# Miccrocontroller.net
KiCad netlist of a schematic drawn in Altium Designer
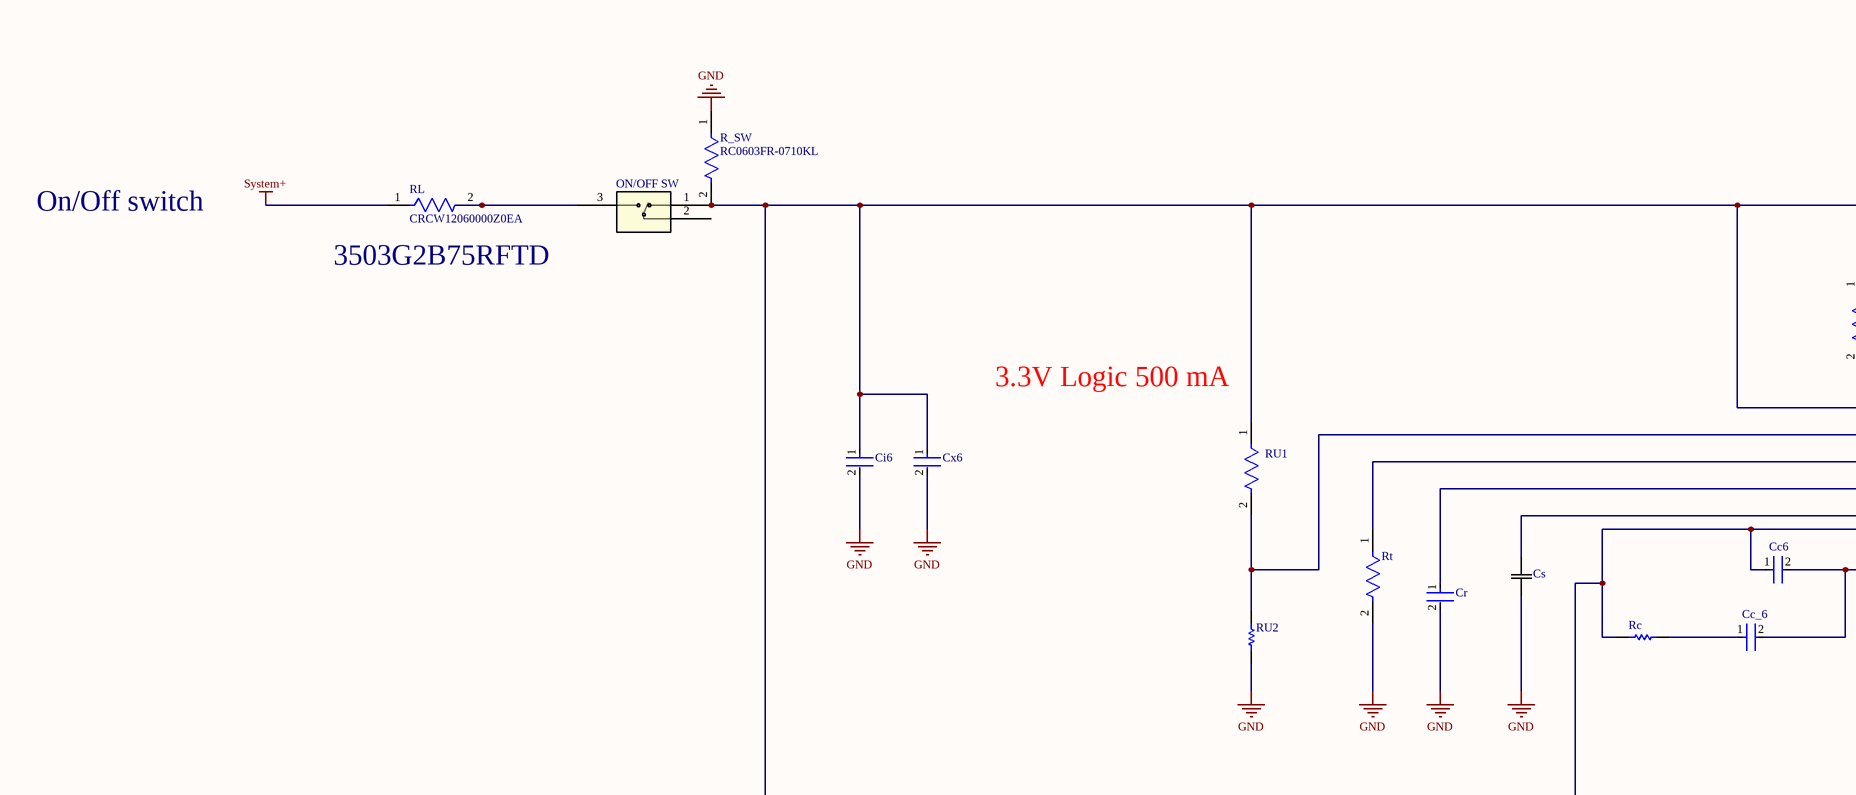
[diagram p0: Miccrocontroller.SchDoc, top left]
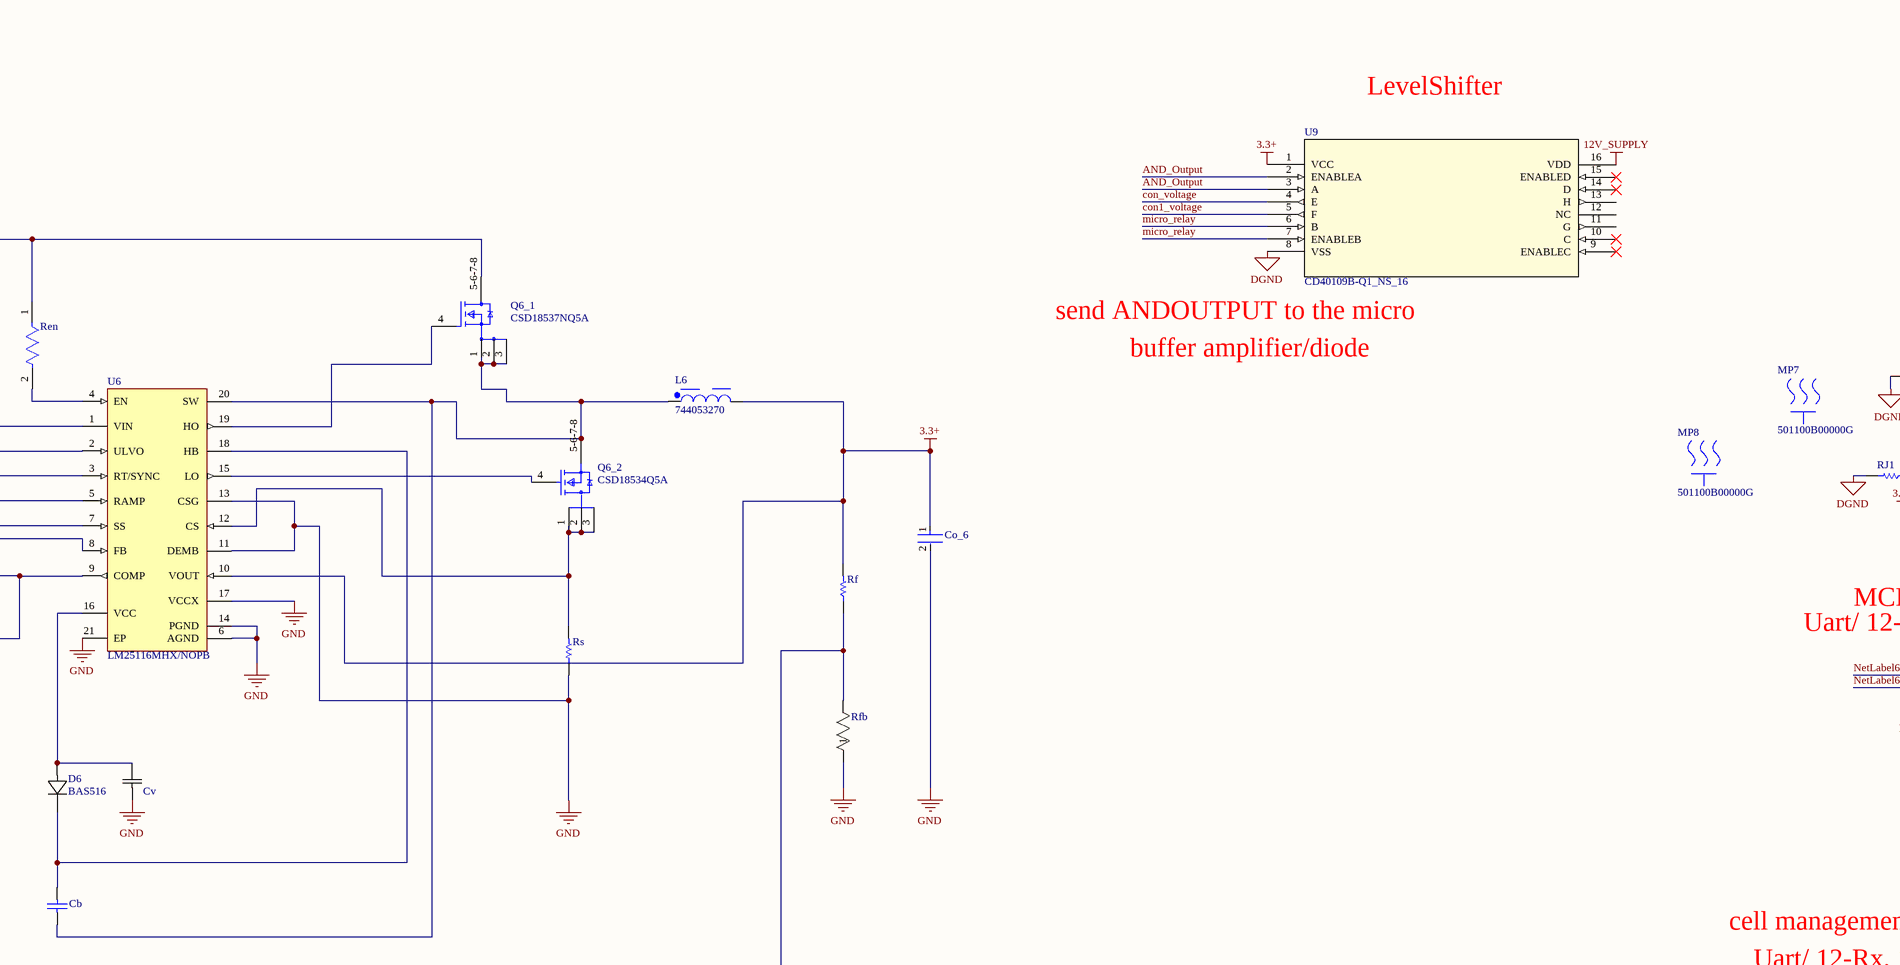
[diagram p1: Miccrocontroller.SchDoc, top middle]
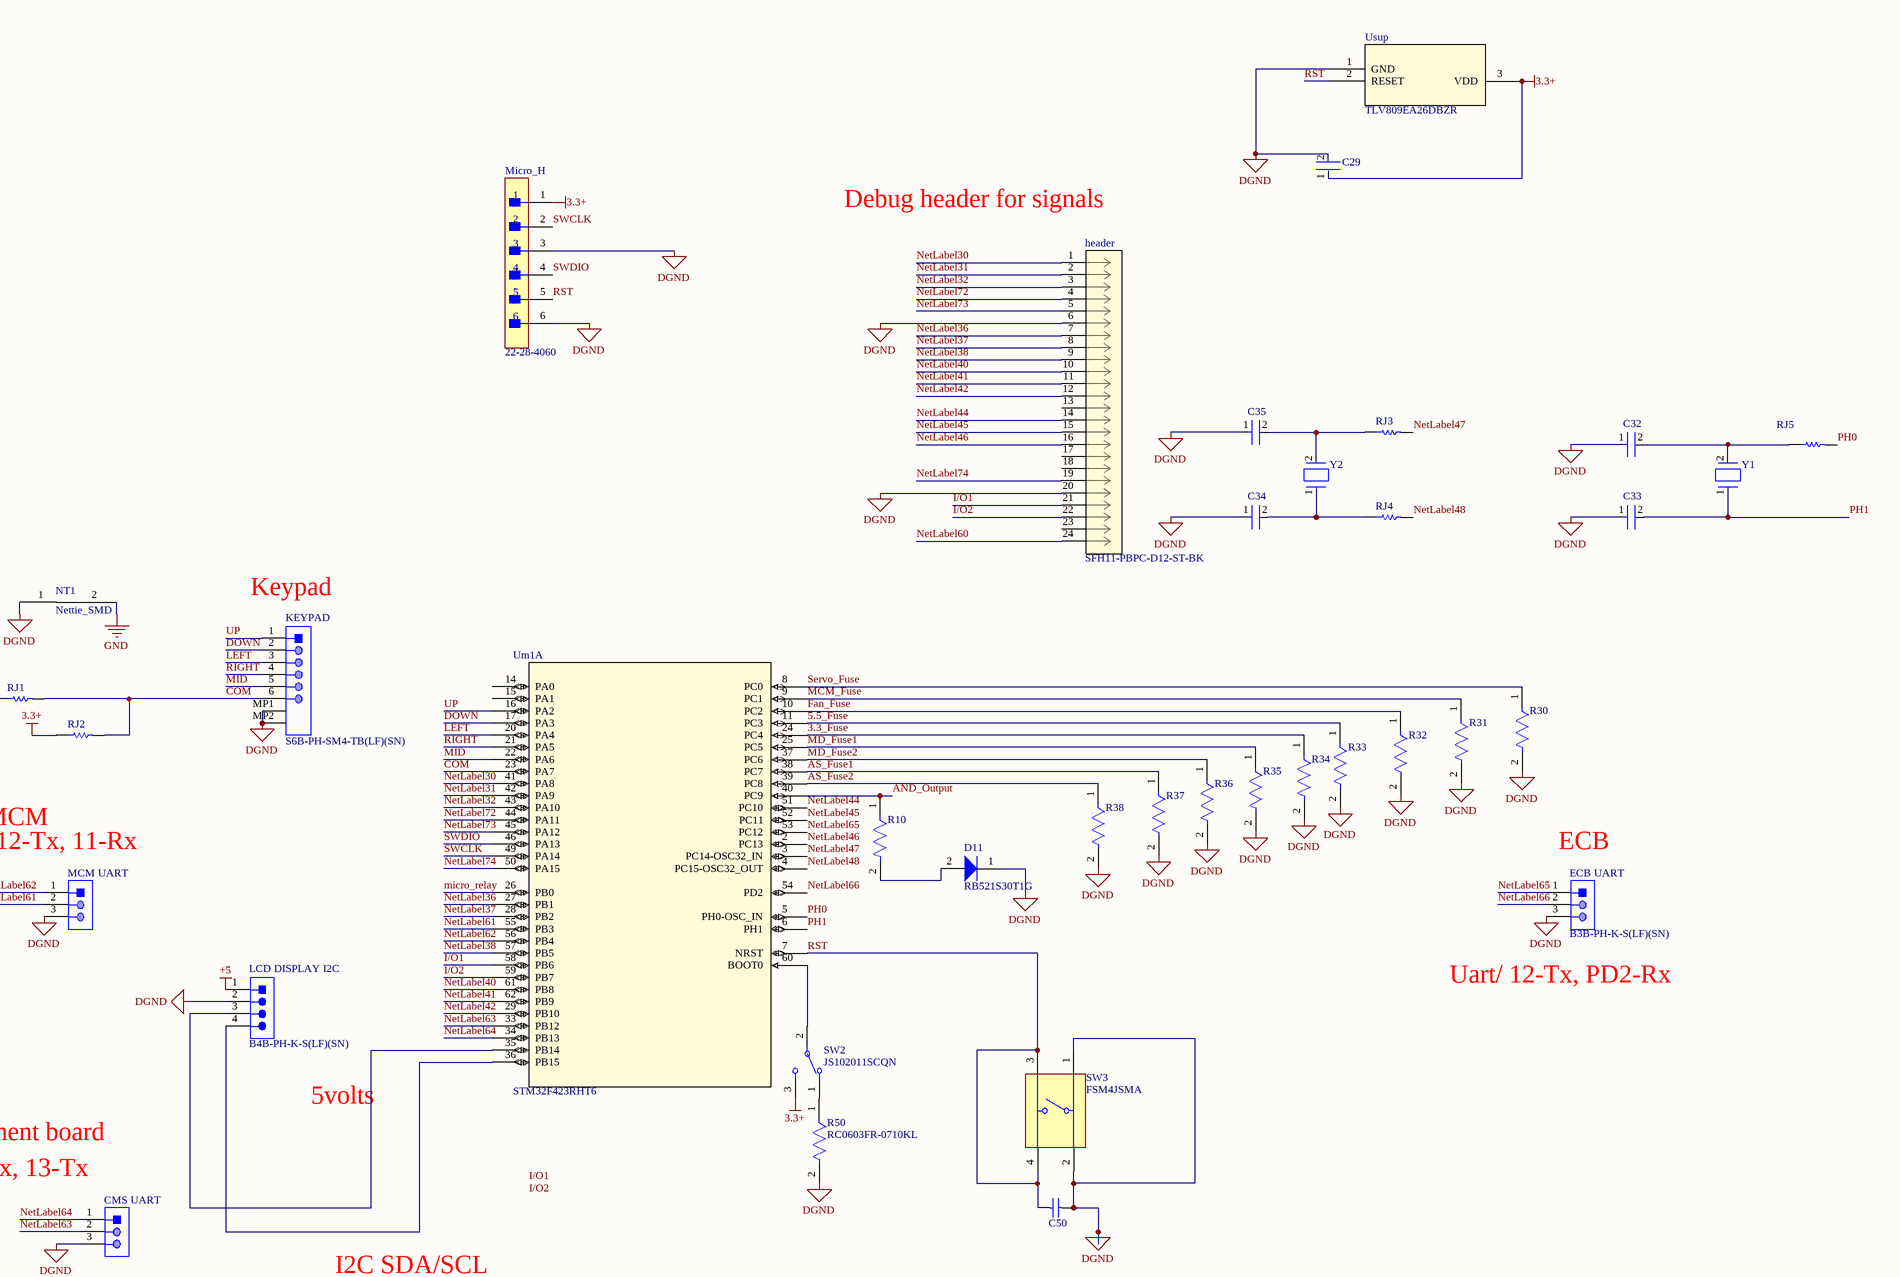
[diagram p2: Miccrocontroller.SchDoc, top right]
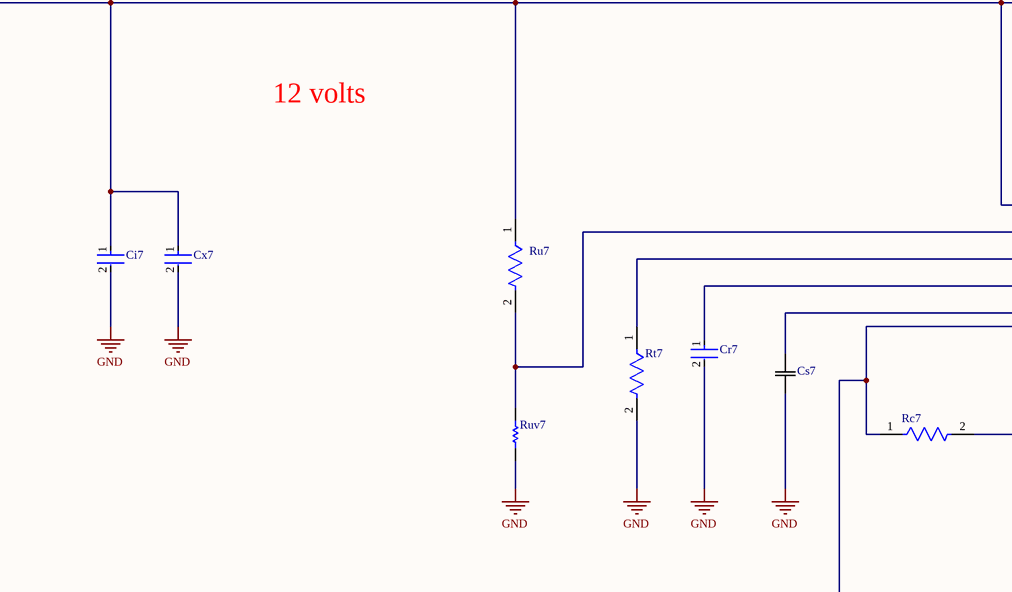
[diagram p3: Miccrocontroller.SchDoc, bottom left]
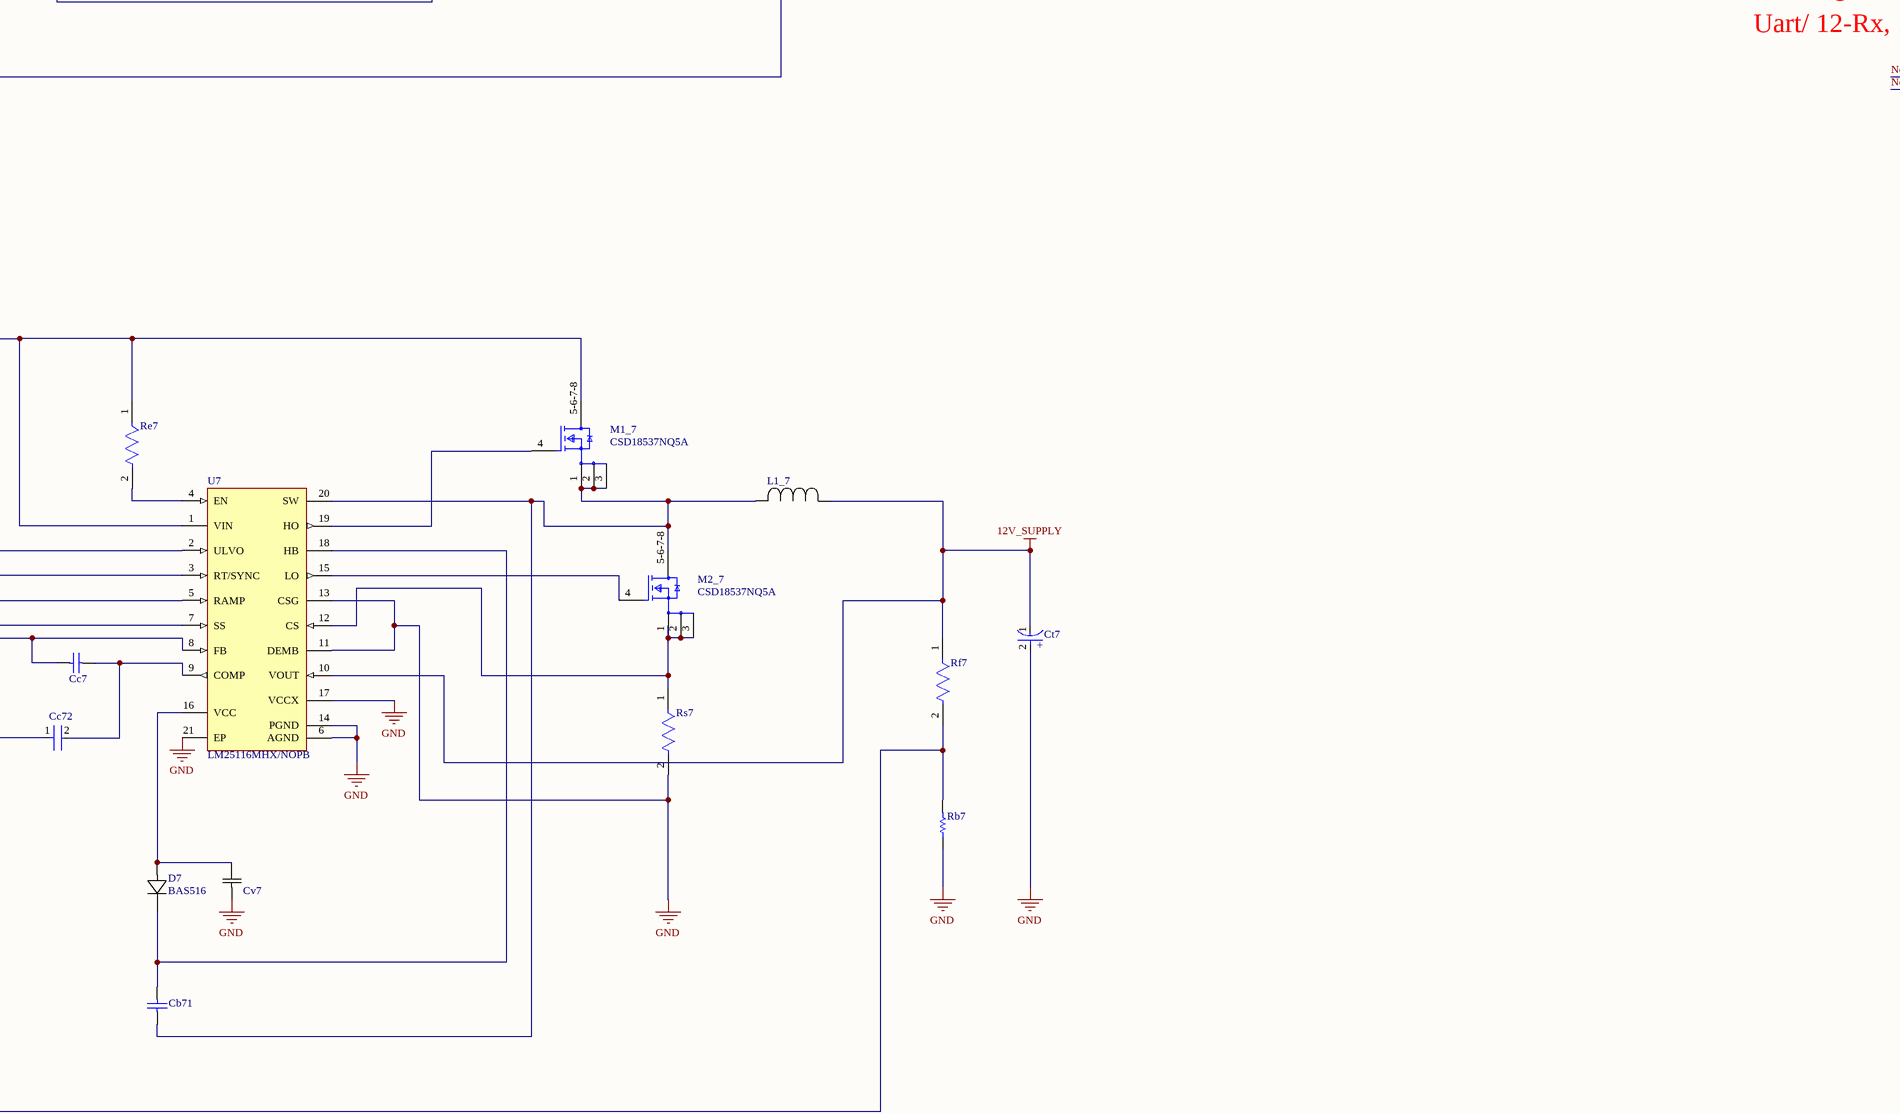
[diagram p4: Miccrocontroller.SchDoc, bottom middle]
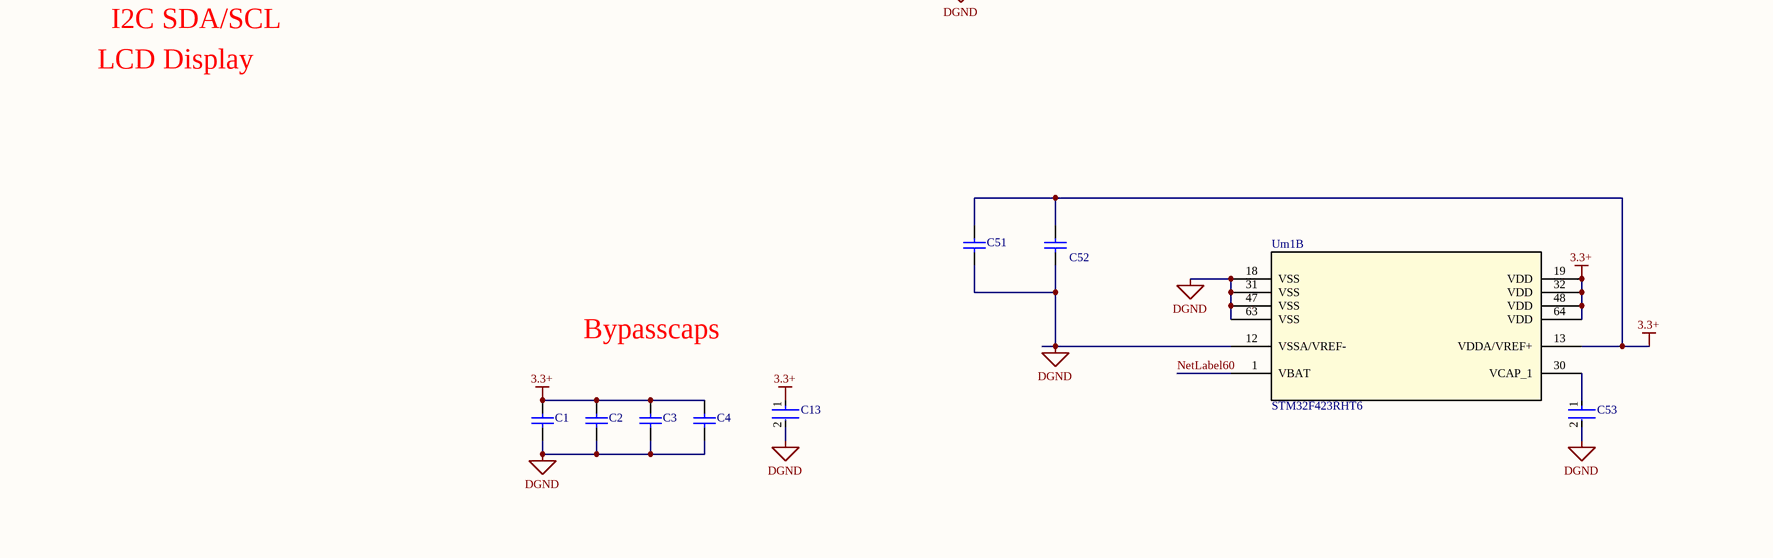
[diagram p5: Miccrocontroller.SchDoc, bottom right]

(export (version "E")
  (design (tool "Eeschema 10.0.6"))
  (components
    (comp (ref "C1")
      (value "06035C104KAT4A")
      (footprint "CAPC1608X90X35LL15T15")
      (fields (field (name "MANUFACTURER") "AVX Interconnect / Elco"))
      (libsource (lib "Altium Content Vault") (part "CAP"))
    )
    (comp (ref "C2")
      (value "06035C104KAT4A")
      (footprint "CAPC1608X90X35LL15T15")
      (fields (field (name "MANUFACTURER") "AVX Interconnect / Elco"))
      (libsource (lib "Altium Content Vault") (part "CAP"))
    )
    (comp (ref "C3")
      (value "06035C104KAT4A")
      (footprint "CAPC1608X90X35LL15T15")
      (fields (field (name "MANUFACTURER") "AVX Interconnect / Elco"))
      (libsource (lib "Altium Content Vault") (part "CAP"))
    )
    (comp (ref "C4")
      (value "06035C104KAT4A")
      (footprint "CAPC1608X90X35LL15T15")
      (fields (field (name "MANUFACTURER") "AVX Interconnect / Elco"))
      (libsource (lib "Altium Content Vault") (part "CAP"))
    )
    (comp (ref "C13")
      (value "GRM188R61E475KE11D")
      (footprint "FP-GRM188-0_15-IPC_C")
      (description "Chip Multilayer Ceramic Capacitors for General Purpose, 0603, 4.7uF, X5R, 15%, 10%, 25V")
      (fields (field (name "VOLTAGE") "25V") (field (name "TOLERANCE") "10%"))
      (libsource (lib "Altium Content Vault") (part "02cd4be3c70576c341d710602a673aa"))
    )
    (comp (ref "C29")
      (value "GRM155R71C104KA88D")
      (footprint "FP-GRM15-MFG")
      (description "CAP CER 0.1UF 16V X7R 0402")
      (fields
        (field (name "TOLERANCE") "10%")
        (field (name "OCTOPART") "https://octopart.com/grm155r71c104ka88d-murata-196880")
      )
      (libsource (lib "Altium Content Vault") (part "236180d848d6139a670b325ea6854c9"))
    )
    (comp (ref "C32")
      (value "C0805C180J5GACTU")
      (footprint "FP-C0805C-DN-MFG")
      (description "CAP CER 18PF 50V C0G/NP0 0805")
      (fields
        (field (name "OCTOPART") "https://octopart.com/c0805c180j5gactu-kemet-144810")
        (field (name "TOLERANCE") "0.05")
      )
      (libsource (lib "Altium Content Vault") (part "b4654b650e69147ec39a6b967a45e02"))
    )
    (comp (ref "C33")
      (value "C0805C180J5GACTU")
      (footprint "FP-C0805C-DN-MFG")
      (description "CAP CER 18PF 50V C0G/NP0 0805")
      (fields
        (field (name "OCTOPART") "https://octopart.com/c0805c180j5gactu-kemet-144810")
        (field (name "TOLERANCE") "0.05")
      )
      (libsource (lib "Altium Content Vault") (part "b4654b650e69147ec39a6b967a45e02"))
    )
    (comp (ref "C34")
      (value "GJM1555C1H1R5BB01D")
      (footprint "FP-GJM155-0_05-IPC_C")
      (description "Multi-Layer Ceramic Capacitor 1.5pF C0G  ±0.1pF 0402 Paper T/R")
      (fields (field (name "VOLTAGE") "50V"))
      (libsource (lib "Altium Content Vault") (part "02cd4be3c70576c341d710602a673aa"))
    )
    (comp (ref "C35")
      (value "GJM1555C1H1R5BB01D")
      (footprint "FP-GJM155-0_05-IPC_C")
      (description "Multi-Layer Ceramic Capacitor 1.5pF C0G  ±0.1pF 0402 Paper T/R")
      (fields (field (name "VOLTAGE") "50V"))
      (libsource (lib "Altium Content Vault") (part "02cd4be3c70576c341d710602a673aa"))
    )
    (comp (ref "C50")
      (value "06035C104KAT4A")
      (footprint "CAPC1608X90X35LL15T15")
      (fields (field (name "MANUFACTURER") "AVX Interconnect / Elco"))
      (libsource (lib "Altium Content Vault") (part "CAP"))
    )
    (comp (ref "C51")
      (value "C0603C105K3RACTU")
      (footprint "CAPC1608X87X35LL15T15")
      (fields (field (name "MANUFACTURER") "Kemet"))
      (libsource (lib "Altium Content Vault") (part "CAP"))
    )
    (comp (ref "C52")
      (value "06035C104KAT4A")
      (footprint "CAPC1608X90X35LL15T15")
      (fields (field (name "MANUFACTURER") "AVX Interconnect / Elco"))
      (libsource (lib "Altium Content Vault") (part "CAP"))
    )
    (comp (ref "C53")
      (value "GRM188R71A225KE15D")
      (footprint "FP-GRM188-0_1-e0_2_0_5-MFG")
      (description "Chip Multilayer Ceramic Capacitors for General Purpose, 0603, 2.2uF, X7R, 15%, 10%, 10V")
      (fields (field (name "VOLTAGE") "10V") (field (name "TOLERANCE") "10%"))
      (libsource (lib "Altium Content Vault") (part "11868f565c42a9108669ba33697ecf6"))
    )
    (comp (ref "Cb")
      (value "08053C104K4T2A")
      (footprint "CAPC2013X140X50LL20T25")
      (fields (field (name "MANUFACTURER") "AVX Interconnect / Elco"))
      (libsource (lib "Altium Content Vault") (part "CAP"))
    )
    (comp (ref "Cb71")
      (value "08053C104K4T2A")
      (footprint "CAPC2013X140X50LL20T25")
      (fields (field (name "MANUFACTURER") "AVX Interconnect / Elco"))
      (libsource (lib "Altium Content Vault") (part "CAP"))
    )
    (comp (ref "Cc6")
      (value "C0805C100M4GACTU")
      (footprint "FP-C0805C-DN-MFG")
      (description "CAP CER 10PF 16V 20% NP0 0805")
      (fields
        (field (name "OCTOPART") "https://octopart.com/c0805c100m4gactu-kemet-16430157")
        (field (name "TOLERANCE") "0.2")
      )
      (libsource (lib "Altium Content Vault") (part "b4654b650e69147ec39a6b967a45e02"))
    )
    (comp (ref "Cc7")
      (value "GRM1555C1E5R1CA01D")
      (footprint "CAPC1005X55X25LL05T10")
      (fields (field (name "MANUFACTURER") "Murata"))
      (libsource (lib "Altium Content Vault") (part "CAP"))
    )
    (comp (ref "Cc72")
      (value "GRM1555C1H101FA01D")
      (footprint "FP-GRM155-0_05-IPC_C")
      (description "CAP CER 100PF 50V C0G/NP0 0402")
      (fields (field (name "VOLTAGE") "50V") (field (name "TOLERANCE") "1%"))
      (libsource (lib "Altium Content Vault") (part "b4654b650e69147ec39a6b967a45e02"))
    )
    (comp (ref "Cc_6")
      (value "UMK105CG271JV-F")
      (footprint "FP-0402-L_1_0_0_05-W_0_5-IPC_B")
      (description "None")
      (fields (field (name "TOLERANCE") "5%"))
      (libsource (lib "Altium Content Vault") (part "b4654b650e69147ec39a6b967a45e02"))
    )
    (comp (ref "Ci6")
      (value "GRM31CR71H475KA12L")
      (footprint "FP-GRM31C-0_2-e0_3_0_8-IPC_C")
      (description "Chip Multilayer Ceramic Capacitors for General Purpose, 1206, 4.7uF, X7R, 15%, 10%, 50V")
      (fields (field (name "VOLTAGE") "50V") (field (name "TOLERANCE") "10%"))
      (libsource (lib "Altium Content Vault") (part "02cd4be3c70576c341d710602a673aa"))
    )
    (comp (ref "Ci7")
      (value "GRM31CR71H475KA12L")
      (footprint "FP-GRM31C-0_2-e0_3_0_8-IPC_C")
      (description "Chip Multilayer Ceramic Capacitors for General Purpose, 1206, 4.7uF, X7R, 15%, 10%, 50V")
      (fields (field (name "VOLTAGE") "50V") (field (name "TOLERANCE") "10%"))
      (libsource (lib "Altium Content Vault") (part "02cd4be3c70576c341d710602a673aa"))
    )
    (comp (ref "CMS UART")
      (value "B3B-PH-K-S(LF)(SN)")
      (footprint "JST-B3B-PH-K-S-3_V")
      (fields (field (name "MANUFACTURER") "JST"))
      (libsource (lib "Altium Content Vault") (part "CN-1P-M-R3"))
    )
    (comp (ref "Co_6")
      (value "C0805C475K8PACTU")
      (footprint "FP-C0805C475K8PACTU-MFG")
      (description "CAP CER 4.7UF 10V X5R 0805")
      (fields (field (name "TOLERANCE") "10%") (field (name "VOLTAGE") "10V"))
      (libsource (lib "Altium Content Vault") (part "e9c51b7dd13d4faca003ae77663ab08"))
    )
    (comp (ref "Cr")
      (value "GRM1555C1H101FA01D")
      (footprint "FP-GRM155-0_05-IPC_C")
      (description "CAP CER 100PF 50V C0G/NP0 0402")
      (fields (field (name "VOLTAGE") "50V") (field (name "TOLERANCE") "1%"))
      (libsource (lib "Altium Content Vault") (part "b4654b650e69147ec39a6b967a45e02"))
    )
    (comp (ref "Cr7")
      (value "UMK105CG271JV-F")
      (footprint "FP-0402-L_1_0_0_05-W_0_5-IPC_B")
      (description "None")
      (fields (field (name "TOLERANCE") "5%"))
      (libsource (lib "Altium Content Vault") (part "b4654b650e69147ec39a6b967a45e02"))
    )
    (comp (ref "Cs")
      (value "CGA4J2C0G1H333J125AA")
      (footprint "CAP_2012_TDK-M")
      (description "No Description Available")
      (libsource (lib "CGA4J2C0G1H333J125AA") (part "CGA4J2C0G1H333J125AA"))
    )
    (comp (ref "Cs7")
      (value "CGA4J2C0G1H333J125AA")
      (footprint "CAP_2012_TDK-M")
      (description "No Description Available")
      (libsource (lib "CGA4J2C0G1H333J125AA") (part "CGA4J2C0G1H333J125AA"))
    )
    (comp (ref "Ct7")
      (value "25SVPF27MX")
      (footprint "FP-OS-CON-SMT-B6-MFG")
      (description "Conductive Polymer Aluminum Solid Capacitors (OS-CON) 27uF ±20% 25V")
      (fields (field (name "VOLTAGE") "25V") (field (name "TOLERANCE") "20%"))
      (libsource (lib "Altium Content Vault") (part "a00bbbee19879c290e62620ae7e47b1"))
    )
    (comp (ref "Cv")
      (value "TMK212BJ105KG-T")
      (footprint "CAP_TMK212BJ105KG-T_TAY")
      (description "No Description Available")
      (libsource (lib "TMK212BJ105KG-T") (part "TMK212BJ105KG-T"))
    )
    (comp (ref "Cv7")
      (value "TMK212BJ105KG-T")
      (footprint "CAP_TMK212BJ105KG-T_TAY")
      (description "No Description Available")
      (libsource (lib "TMK212BJ105KG-T") (part "TMK212BJ105KG-T"))
    )
    (comp (ref "Cx6")
      (value "C0805C104M5RACTU")
      (footprint "FP-C0805C-DN-MFG")
      (description "CAP CER 0.1UF 50V X7R 0805")
      (fields
        (field (name "TOLERANCE") "0.2")
        (field (name "OCTOPART") "https://octopart.com/c0805c104m5ractu-kemet-129379")
      )
      (libsource (lib "Altium Content Vault") (part "b4654b650e69147ec39a6b967a45e02"))
    )
    (comp (ref "Cx7")
      (value "C0805C104M5RACTU")
      (footprint "FP-C0805C-DN-MFG")
      (description "CAP CER 0.1UF 50V X7R 0805")
      (fields
        (field (name "TOLERANCE") "0.2")
        (field (name "OCTOPART") "https://octopart.com/c0805c104m5ractu-kemet-129379")
      )
      (libsource (lib "Altium Content Vault") (part "b4654b650e69147ec39a6b967a45e02"))
    )
    (comp (ref "D6")
      (value "BAS516")
      (footprint "SOD523_NEX")
      (description "No Description Available")
      (libsource (lib "BAS516") (part "BAS516"))
    )
    (comp (ref "D7")
      (value "BAS516")
      (footprint "SOD523_NEX")
      (description "No Description Available")
      (libsource (lib "BAS516") (part "BAS516"))
    )
    (comp (ref "D11")
      (value "RB521S30T1G")
      (footprint "ONSC-SOD-523-2-502-01_V")
      (description "Schottky Barrier Diode, 2-Pin SOD-523, Pb-Free, Tape and Reel")
      (fields (field (name "MANUFACTURER") "On Semiconductor"))
      (libsource (lib "Altium Content Vault") (part "ONSC-D-K1A2-2"))
    )
    (comp (ref "ECB UART")
      (value "B3B-PH-K-S(LF)(SN)")
      (footprint "JST-B3B-PH-K-S-3_V")
      (fields (field (name "MANUFACTURER") "JST"))
      (libsource (lib "Altium Content Vault") (part "CN-1P-M-R3"))
    )
    (comp (ref "header")
      (value "SFH11-PBPC-D12-ST-BK")
      (footprint "CONN_SFH11-PBPC-D12-ST-BK")
      (description "No Description Available")
      (libsource (lib "SFH11-PBPC-D12-ST-BK") (part "SFH11-PBPC-D12-ST-BK"))
    )
    (comp (ref "KEYPAD")
      (value "S6B-PH-SM4-TB(LF)(SN)")
      (footprint "JST-S6B-PH-SM4-TB(LF)(SN)_V")
      (description "Male Header, Pitch 2 mm, 1 x 6 Position, Height 5.5 mm, -25 to 85 degC")
      (fields (field (name "MANUFACTURER") "JST"))
      (libsource (lib "Altium Content Vault") (part "CN-1P-2M-R6"))
    )
    (comp (ref "L1_7")
      (value "MSS1038-123MLB")
      (footprint "IND_MSS1038_COC")
      (description "No Description Available")
      (libsource (lib "MSS1038-123MLB") (part "MSS1038-123MLB"))
    )
    (comp (ref "L6")
      (value "744053270")
      (footprint "WE-TPC_5828")
      (libsource (lib "Altium Content Vault") (part "Inductor - 2"))
    )
    (comp (ref "LCD DISPLAY I2C")
      (value "B4B-PH-K-S(LF)(SN)")
      (footprint "JST-B4B-PH-K-S_V")
      (fields (field (name "MANUFACTURER") "JST"))
      (libsource (lib "Altium Content Vault") (part "CN-1P-M-R4"))
    )
    (comp (ref "M1_7")
      (value "CSD18537NQ5A")
      (footprint "FP-DQJ0008A-MFG")
      (description "MOSFET N-CH 60V 50A 8SON")
      (libsource (lib "Altium Content Vault") (part "7382af88e928fdc71488234cfaaf11c"))
    )
    (comp (ref "M2_7")
      (value "CSD18537NQ5A")
      (footprint "FP-DQJ0008A-MFG")
      (description "MOSFET N-CH 60V 50A 8SON")
      (libsource (lib "Altium Content Vault") (part "7382af88e928fdc71488234cfaaf11c"))
    )
    (comp (ref "MCM UART")
      (value "B3B-PH-K-S(LF)(SN)")
      (footprint "JST-B3B-PH-K-S-3_V")
      (fields (field (name "MANUFACTURER") "JST"))
      (libsource (lib "Altium Content Vault") (part "CN-1P-M-R3"))
    )
    (comp (ref "Micro_H")
      (value "22-28-4060")
      (footprint "FP-22-28-4060-MFG")
      (description "CONN HEADER VERT 6POS 2.54MM")
      (libsource (lib "Altium Content Vault") (part "f2cb566baf1c37ab5a3b8e90bbeafd6"))
    )
    (comp (ref "MP7")
      (value "501100B00000G")
      (footprint "FP-501100B00000G-MFG")
      (description "HEATSINK 14-DIP/16-DIP")
      (libsource (lib "Altium Content Vault") (part "fbfed2df5ada343d60df597a9663bc7"))
    )
    (comp (ref "MP8")
      (value "501100B00000G")
      (footprint "FP-501100B00000G-MFG")
      (description "HEATSINK 14-DIP/16-DIP")
      (libsource (lib "Altium Content Vault") (part "fbfed2df5ada343d60df597a9663bc7"))
    )
    (comp (ref "NT1")
      (value "Nettie_SMD")
      (footprint "Nettie_SMD")
      (libsource (lib "Schlib1") (part "Nettie_SMD"))
    )
    (comp (ref "ON/OFF SW")
      (value "100SP1T1B4M2QE")
      (footprint "100SP1T1_EWI")
      (description "No Description Available")
      (libsource (lib "100SP1T1B4M2QE") (part "100SP1T1B4M2QE"))
    )
    (comp (ref "Q6_1")
      (value "CSD18537NQ5A")
      (footprint "FP-DQJ0008A-MFG")
      (description "MOSFET N-CH 60V 50A 8SON")
      (libsource (lib "Altium Content Vault") (part "7382af88e928fdc71488234cfaaf11c"))
    )
    (comp (ref "Q6_2")
      (value "CSD18534Q5A")
      (footprint "FP-DQJ0008A-MFG")
      (description "MOSFET N-CH 60V 8SON")
      (fields
        (field (name "OCTOPART") "https://octopart.com/csd18534q5a-texas+instruments-22791040")
        (field (name "MANUFACTURER") "Texas Instruments")
      )
      (libsource (lib "Altium Content Vault") (part "2b493a92fcdc54dddf28a3aa2503ef1"))
    )
    (comp (ref "R10")
      (value "RC0603FR-0710KL")
      (footprint "FP-RC0603-0_55-IPC_C")
      (description "RES 10K OHM 1% 1/10W 0603")
      (fields (field (name "TOLERANCE") "1%"))
      (libsource (lib "Altium Content Vault") (part "1029c3af85768c4190bb7ad29bc67b5"))
    )
    (comp (ref "R30")
      (value "RC0603FR-0710KL")
      (footprint "FP-RC0603-0_55-IPC_C")
      (description "RES 10K OHM 1% 1/10W 0603")
      (fields (field (name "TOLERANCE") "1%"))
      (libsource (lib "Altium Content Vault") (part "1029c3af85768c4190bb7ad29bc67b5"))
    )
    (comp (ref "R31")
      (value "RC0603FR-0710KL")
      (footprint "FP-RC0603-0_55-IPC_C")
      (description "RES 10K OHM 1% 1/10W 0603")
      (fields (field (name "TOLERANCE") "1%"))
      (libsource (lib "Altium Content Vault") (part "1029c3af85768c4190bb7ad29bc67b5"))
    )
    (comp (ref "R32")
      (value "RC0603FR-0710KL")
      (footprint "FP-RC0603-0_55-IPC_C")
      (description "RES 10K OHM 1% 1/10W 0603")
      (fields (field (name "TOLERANCE") "1%"))
      (libsource (lib "Altium Content Vault") (part "1029c3af85768c4190bb7ad29bc67b5"))
    )
    (comp (ref "R33")
      (value "RC0603FR-0710KL")
      (footprint "FP-RC0603-0_55-IPC_C")
      (description "RES 10K OHM 1% 1/10W 0603")
      (fields (field (name "TOLERANCE") "1%"))
      (libsource (lib "Altium Content Vault") (part "1029c3af85768c4190bb7ad29bc67b5"))
    )
    (comp (ref "R34")
      (value "RC0603FR-0710KL")
      (footprint "FP-RC0603-0_55-IPC_C")
      (description "RES 10K OHM 1% 1/10W 0603")
      (fields (field (name "TOLERANCE") "1%"))
      (libsource (lib "Altium Content Vault") (part "1029c3af85768c4190bb7ad29bc67b5"))
    )
    (comp (ref "R35")
      (value "RC0603FR-0710KL")
      (footprint "FP-RC0603-0_55-IPC_C")
      (description "RES 10K OHM 1% 1/10W 0603")
      (fields (field (name "TOLERANCE") "1%"))
      (libsource (lib "Altium Content Vault") (part "1029c3af85768c4190bb7ad29bc67b5"))
    )
    (comp (ref "R36")
      (value "RC0603FR-0710KL")
      (footprint "FP-RC0603-0_55-IPC_C")
      (description "RES 10K OHM 1% 1/10W 0603")
      (fields (field (name "TOLERANCE") "1%"))
      (libsource (lib "Altium Content Vault") (part "1029c3af85768c4190bb7ad29bc67b5"))
    )
    (comp (ref "R37")
      (value "RC0603FR-0710KL")
      (footprint "FP-RC0603-0_55-IPC_C")
      (description "RES 10K OHM 1% 1/10W 0603")
      (fields (field (name "TOLERANCE") "1%"))
      (libsource (lib "Altium Content Vault") (part "1029c3af85768c4190bb7ad29bc67b5"))
    )
    (comp (ref "R38")
      (value "RC0603FR-0710KL")
      (footprint "FP-RC0603-0_55-IPC_C")
      (description "RES 10K OHM 1% 1/10W 0603")
      (fields (field (name "TOLERANCE") "1%"))
      (libsource (lib "Altium Content Vault") (part "1029c3af85768c4190bb7ad29bc67b5"))
    )
    (comp (ref "R50")
      (value "RC0603FR-0710KL")
      (footprint "FP-RC0603-0_55-IPC_C")
      (description "RES 10K OHM 1% 1/10W 0603")
      (fields (field (name "TOLERANCE") "1%"))
      (libsource (lib "Altium Content Vault") (part "1029c3af85768c4190bb7ad29bc67b5"))
    )
    (comp (ref "Rb7")
      (value "ERJ-6ENF9761V")
      (footprint "RESC2013X70X40ML20T20")
      (fields (field (name "MANUFACTURER") "Panasonic"))
      (libsource (lib "Altium Content Vault") (part "RES"))
    )
    (comp (ref "Rc")
      (value "RC0402FR-0768K1L")
      (footprint "RESC1005X40X25NL05T10")
      (fields (field (name "MANUFACTURER") "Yageo / Phycomp"))
      (libsource (lib "Altium Content Vault") (part "RES"))
    )
    (comp (ref "Rc7")
      (value "CRCW0402191KFKED")
      (footprint "FP-CRCW0402-e3-IPC_C")
      (description "RES Thick Film, 191kΩ, 1%, 0.063W, 100ppm/°C, 0402")
      (fields (field (name "TOLERANCE") "1%"))
      (libsource (lib "Altium Content Vault") (part "1029c3af85768c4190bb7ad29bc67b5"))
    )
    (comp (ref "Re7")
      (value "CRCW04021M00FKED")
      (footprint "FP-CRCW0402-e3-MFG")
      (description "RES Thick Film, 1MΩ, 1%, 0.063W, 100ppm/°C, 0402")
      (fields (field (name "TOLERANCE") "1%"))
      (libsource (lib "Altium Content Vault") (part "1029c3af85768c4190bb7ad29bc67b5"))
    )
    (comp (ref "Ren")
      (value "CRCW04021M00FKED")
      (footprint "FP-CRCW0402-e3-MFG")
      (description "RES Thick Film, 1MΩ, 1%, 0.063W, 100ppm/°C, 0402")
      (fields (field (name "TOLERANCE") "1%"))
      (libsource (lib "Altium Content Vault") (part "1029c3af85768c4190bb7ad29bc67b5"))
    )
    (comp (ref "Rf")
      (value "ERJ-6ENF1872V")
      (footprint "RESC2013X70X40LL20T20")
      (fields (field (name "MANUFACTURER") "Panasonic"))
      (libsource (lib "Altium Content Vault") (part "RES"))
    )
    (comp (ref "Rf7")
      (value "AC0402FR-0786K6L")
      (footprint "FP-AC0402-IPC_B")
      (description "RES 86.6kΩ ±1% 0.063W 0402")
      (fields (field (name "TOLERANCE") "1%"))
      (libsource (lib "Altium Content Vault") (part "1029c3af85768c4190bb7ad29bc67b5"))
    )
    (comp (ref "Rfb")
      (value "RNCF0805BTE10K4")
      (footprint "RES_RNCF0805_STP")
      (description "No Description Available")
      (libsource (lib "RNCF0805BTE10K4") (part "RNCF0805BTE10K4"))
    )
    (comp (ref "RJ1")
      (value "CRCW08050000Z0EA")
      (footprint "RESC2013X50X30LL20T20")
      (fields (field (name "MANUFACTURER") "Vishay Dale"))
      (libsource (lib "Altium Content Vault") (part "RES"))
    )
    (comp (ref "RJ2")
      (value "CRCW08050000Z0EA")
      (footprint "RESC2013X50X30LL20T20")
      (fields (field (name "MANUFACTURER") "Vishay Dale"))
      (libsource (lib "Altium Content Vault") (part "RES"))
    )
    (comp (ref "RJ3")
      (value "CRCW08050000Z0EA")
      (footprint "RESC2013X50X30LL20T20")
      (fields (field (name "MANUFACTURER") "Vishay Dale"))
      (libsource (lib "Altium Content Vault") (part "RES"))
    )
    (comp (ref "RJ4")
      (value "CRCW08050000Z0EA")
      (footprint "RESC2013X50X30LL20T20")
      (fields (field (name "MANUFACTURER") "Vishay Dale"))
      (libsource (lib "Altium Content Vault") (part "RES"))
    )
    (comp (ref "RJ5")
      (value "CRCW08050000Z0EA")
      (footprint "RESC2013X50X30LL20T20")
      (fields (field (name "MANUFACTURER") "Vishay Dale"))
      (libsource (lib "Altium Content Vault") (part "RES"))
    )
    (comp (ref "RL")
      (value "CRCW12060000Z0EA")
      (footprint "FP-CRCW1206-e3-IPC_C")
      (description "RES Thick Film, 0Ω, 0.25W, 1206")
      (fields (field (name "TOLERANCE") "1%"))
      (libsource (lib "Altium Content Vault") (part "1029c3af85768c4190bb7ad29bc67b5"))
    )
    (comp (ref "Rs")
      (value "ERJ-3RSFR15V")
      (footprint "RESC1608X55X30ML15T15")
      (fields (field (name "MANUFACTURER") "Panasonic"))
      (libsource (lib "Altium Content Vault") (part "RES"))
    )
    (comp (ref "Rs7")
      (value "CSR1206FK15L0")
      (footprint "FP-CSR1206-IPC_B")
      (description "General Purpose Thick Film Chip Resistor, 1206, 15mΩ, 1%, 0.5W")
      (fields (field (name "TOLERANCE") "1%"))
      (libsource (lib "Altium Content Vault") (part "1029c3af85768c4190bb7ad29bc67b5"))
    )
    (comp (ref "Rt")
      (value "CRCW04025K23FKED")
      (footprint "FP-CRCW0402-e3-IPC_C")
      (description "RES Thick Film, 5.23kΩ, 1%, 0.063W, 100ppm/°C, 0402")
      (fields (field (name "TOLERANCE") "1%"))
      (libsource (lib "Altium Content Vault") (part "1029c3af85768c4190bb7ad29bc67b5"))
    )
    (comp (ref "Rt7")
      (value "CRCW04025K23FKED")
      (footprint "FP-CRCW0402-e3-IPC_C")
      (description "RES Thick Film, 5.23kΩ, 1%, 0.063W, 100ppm/°C, 0402")
      (fields (field (name "TOLERANCE") "1%"))
      (libsource (lib "Altium Content Vault") (part "1029c3af85768c4190bb7ad29bc67b5"))
    )
    (comp (ref "RU1")
      (value "CRCW080541K2FKEA")
      (footprint "Vishay_CRCW0805-e3_MFG")
      (fields (field (name "TOLERANCE") "1%"))
      (libsource (lib "Altium Content Vault") (part "CRCW080541K2FKEA"))
    )
    (comp (ref "RU2")
      (value "ERJ-6ENF2491V")
      (footprint "RESC2013X70X40LL20T20")
      (fields (field (name "MANUFACTURER") "Panasonic"))
      (libsource (lib "Altium Content Vault") (part "RES"))
    )
    (comp (ref "Ru7")
      (value "CRCW080541K2FKEA")
      (footprint "Vishay_CRCW0805-e3_MFG")
      (fields (field (name "TOLERANCE") "1%"))
      (libsource (lib "Altium Content Vault") (part "CRCW080541K2FKEA"))
    )
    (comp (ref "Ruv7")
      (value "ERJ-6ENF2491V")
      (footprint "RESC2013X70X40LL20T20")
      (fields (field (name "MANUFACTURER") "Panasonic"))
      (libsource (lib "Altium Content Vault") (part "RES"))
    )
    (comp (ref "R_SW")
      (value "RC0603FR-0710KL")
      (footprint "FP-RC0603-0_55-IPC_C")
      (description "RES 10K OHM 1% 1/10W 0603")
      (fields (field (name "TOLERANCE") "1%"))
      (libsource (lib "Altium Content Vault") (part "1029c3af85768c4190bb7ad29bc67b5"))
    )
    (comp (ref "SW2")
      (value "JS102011SCQN")
      (footprint "FP-JS102011SCQN-MFG")
      (description "SWITCH SLIDE SPDT 300MA 6V")
      (libsource (lib "Altium Content Vault") (part "39e195cbbadc85d1df0d7eb6847d379"))
    )
    (comp (ref "SW3")
      (value "FSM4JSMA")
      (footprint "TECO-FSM4JSMA_V")
      (description "Swicth, SPST, 24 V, -35 to 85 degC, 4-Pin SMD, RoHS, Tape and Reel")
      (fields (field (name "MANUFACTURER") "TE Connectivity"))
      (libsource (lib "Altium Content Vault") (part "SW-SPST-4_A"))
    )
    (comp (ref "U6")
      (value "LM25116MHX/NOPB")
      (footprint "PWP0020A_N")
      (description "Wide Range Synchronous Buck Controller, 20-pin TSSOP-EP, Pb-Free")
      (fields (field (name "MANUFACTURER") "Texas Instruments"))
      (libsource (lib "Altium Content Vault") (part "PM-REG-LM25116MH-21"))
    )
    (comp (ref "U7")
      (value "LM25116MHX/NOPB")
      (footprint "PWP0020A_N")
      (description "Wide Range Synchronous Buck Controller, 20-pin TSSOP-EP, Pb-Free")
      (fields (field (name "MANUFACTURER") "Texas Instruments"))
      (libsource (lib "Altium Content Vault") (part "PM-REG-LM25116MH-21"))
    )
    (comp (ref "U9")
      (value "CD40109B-Q1_NS_16")
      (footprint "NS16_TEX")
      (description "No Description Available")
      (libsource (lib "CD40109B-Q1_NS_16") (part "CD40109B-Q1_NS_16"))
    )
    (comp (ref "Um1")
      (value "STM32F423RHT6")
      (footprint "PcbLib1:LQFP64-10x10mm")
      (description "No Description Available")
      (libsource (lib "STM32F423RHT6") (part "STM32F423RHT6"))
    )
    (comp (ref "Usup")
      (value "TLV809EA26DBZR")
      (footprint "SOT_26DBZR_TEX-M")
      (description "No Description Available")
      (libsource (lib "TLV809EA26DBZR") (part "TLV809EA26DBZR"))
    )
    (comp (ref "Y1")
      (value "ABM7-25.000MHZ-D2Y-T")
      (footprint "FP-ABM7-MFG")
      (description "Crystal 25MHz ±20ppm 18pF SMD-2 6mm x 3.5mm")
      (fields (field (name "TOLERANCE") "20ppm"))
      (libsource (lib "Altium Content Vault") (part "c23a69dc6c9e2f18f2079038eb95dd1"))
    )
    (comp (ref "Y2")
      (value "MU00525-32.768K")
      (footprint "FP-NX3215SA-MFG")
      (description "MU00525-32.768K Crystal 32.7680KHZ 6PF SMD")
      (libsource (lib "Altium Content Vault") (part "c23a69dc6c9e2f18f2079038eb95dd1"))
    )
  )
  (nets
    (net (code "1") (name "+5") (class "Default")
      (node (ref "LCD DISPLAY I2C") (pin "1") (pinfunction "1_1") (pintype "passive"))
    )
    (net (code "2") (name "/3.3_Fuse") (class "Default")
      (node (ref "R34") (pin "1") (pinfunction "1_1") (pintype "passive"))
      (node (ref "Um1") (pin "24") (pinfunction "PC4_24") (pintype "input"))
    )
    (net (code "3") (name "/5.5_Fuse") (class "Default")
      (node (ref "R33") (pin "1") (pinfunction "1_1") (pintype "passive"))
      (node (ref "Um1") (pin "11") (pinfunction "PC3_11") (pintype "input"))
    )
    (net (code "4") (name "/AND_Output") (class "Default")
      (node (ref "R10") (pin "1") (pinfunction "1_1") (pintype "passive"))
      (node (ref "U9") (pin "2") (pinfunction "ENABLEA_2") (pintype "input"))
      (node (ref "U9") (pin "3") (pinfunction "A_3") (pintype "input"))
      (node (ref "Um1") (pin "40") (pinfunction "PC9_40") (pintype "input"))
    )
    (net (code "5") (name "/AS_Fuse1") (class "Default")
      (node (ref "R37") (pin "1") (pinfunction "1_1") (pintype "passive"))
      (node (ref "Um1") (pin "38") (pinfunction "PC7_38") (pintype "input"))
    )
    (net (code "6") (name "/AS_Fuse2") (class "Default")
      (node (ref "R38") (pin "1") (pinfunction "1_1") (pintype "passive"))
      (node (ref "Um1") (pin "39") (pinfunction "PC8_39") (pintype "input"))
    )
    (net (code "7") (name "/COM") (class "Default")
      (node (ref "KEYPAD") (pin "6") (pinfunction "6_6") (pintype "passive"))
      (node (ref "RJ1") (pin "2") (pinfunction "2_2") (pintype "passive"))
      (node (ref "RJ2") (pin "2") (pinfunction "2_2") (pintype "passive"))
      (node (ref "Um1") (pin "23") (pinfunction "PA7_23") (pintype "bidirectional"))
    )
    (net (code "8") (name "/DOWN") (class "Default")
      (node (ref "KEYPAD") (pin "2") (pinfunction "2_2") (pintype "passive"))
      (node (ref "Um1") (pin "17") (pinfunction "PA3_17") (pintype "bidirectional"))
    )
    (net (code "9") (name "/Fan_Fuse") (class "Default")
      (node (ref "R32") (pin "1") (pinfunction "1_1") (pintype "passive"))
      (node (ref "Um1") (pin "10") (pinfunction "PC2_10") (pintype "input"))
    )
    (net (code "10") (name "/I{slash}O1") (class "Default")
      (node (ref "Um1") (pin "58") (pinfunction "PB6_58") (pintype "bidirectional"))
      (node (ref "header") (pin "21") (pinfunction "21_21") (pintype "passive"))
    )
    (net (code "11") (name "/I{slash}O2") (class "Default")
      (node (ref "Um1") (pin "59") (pinfunction "PB7_59") (pintype "bidirectional"))
      (node (ref "header") (pin "22") (pinfunction "22_22") (pintype "passive"))
    )
    (net (code "12") (name "/LEFT") (class "Default")
      (node (ref "KEYPAD") (pin "3") (pinfunction "3_3") (pintype "passive"))
      (node (ref "Um1") (pin "20") (pinfunction "PA4_20") (pintype "bidirectional"))
    )
    (net (code "13") (name "/MCM_Fuse") (class "Default")
      (node (ref "R31") (pin "1") (pinfunction "1_1") (pintype "passive"))
      (node (ref "Um1") (pin "9") (pinfunction "PC1_9") (pintype "input"))
    )
    (net (code "14") (name "/MD_Fuse1") (class "Default")
      (node (ref "R35") (pin "1") (pinfunction "1_1") (pintype "passive"))
      (node (ref "Um1") (pin "25") (pinfunction "PC5_25") (pintype "input"))
    )
    (net (code "15") (name "/MD_Fuse2") (class "Default")
      (node (ref "R36") (pin "1") (pinfunction "1_1") (pintype "passive"))
      (node (ref "Um1") (pin "37") (pinfunction "PC6_37") (pintype "input"))
    )
    (net (code "16") (name "/MID") (class "Default")
      (node (ref "KEYPAD") (pin "5") (pinfunction "5_5") (pintype "passive"))
      (node (ref "Um1") (pin "22") (pinfunction "PA6_22") (pintype "bidirectional"))
    )
    (net (code "17") (name "/NetLabel30") (class "Default")
      (node (ref "Um1") (pin "41") (pinfunction "PA8_41") (pintype "bidirectional"))
      (node (ref "header") (pin "1") (pinfunction "1_1") (pintype "passive"))
    )
    (net (code "18") (name "/NetLabel31") (class "Default")
      (node (ref "Um1") (pin "42") (pinfunction "PA9_42") (pintype "bidirectional"))
      (node (ref "header") (pin "2") (pinfunction "2_2") (pintype "passive"))
    )
    (net (code "19") (name "/NetLabel32") (class "Default")
      (node (ref "Um1") (pin "43") (pinfunction "PA10_43") (pintype "bidirectional"))
      (node (ref "header") (pin "3") (pinfunction "3_3") (pintype "passive"))
    )
    (net (code "20") (name "/NetLabel36") (class "Default")
      (node (ref "Um1") (pin "27") (pinfunction "PB1_27") (pintype "bidirectional"))
      (node (ref "header") (pin "7") (pinfunction "7_7") (pintype "passive"))
    )
    (net (code "21") (name "/NetLabel37") (class "Default")
      (node (ref "Um1") (pin "28") (pinfunction "PB2_28") (pintype "bidirectional"))
      (node (ref "header") (pin "8") (pinfunction "8_8") (pintype "passive"))
    )
    (net (code "22") (name "/NetLabel38") (class "Default")
      (node (ref "Um1") (pin "57") (pinfunction "PB5_57") (pintype "bidirectional"))
      (node (ref "header") (pin "9") (pinfunction "9_9") (pintype "passive"))
    )
    (net (code "23") (name "/NetLabel40") (class "Default")
      (node (ref "Um1") (pin "61") (pinfunction "PB8_61") (pintype "bidirectional"))
      (node (ref "header") (pin "10") (pinfunction "10_10") (pintype "passive"))
    )
    (net (code "24") (name "/NetLabel41") (class "Default")
      (node (ref "Um1") (pin "62") (pinfunction "PB9_62") (pintype "bidirectional"))
      (node (ref "header") (pin "11") (pinfunction "11_11") (pintype "passive"))
    )
    (net (code "25") (name "/NetLabel42") (class "Default")
      (node (ref "Um1") (pin "29") (pinfunction "PB10_29") (pintype "bidirectional"))
      (node (ref "header") (pin "12") (pinfunction "12_12") (pintype "passive"))
    )
    (net (code "26") (name "/NetLabel44") (class "Default")
      (node (ref "Um1") (pin "51") (pinfunction "PC10_51") (pintype "bidirectional"))
      (node (ref "header") (pin "14") (pinfunction "14_14") (pintype "passive"))
    )
    (net (code "27") (name "/NetLabel45") (class "Default")
      (node (ref "Um1") (pin "52") (pinfunction "PC11_52") (pintype "bidirectional"))
      (node (ref "header") (pin "15") (pinfunction "15_15") (pintype "passive"))
    )
    (net (code "28") (name "/NetLabel46") (class "Default")
      (node (ref "Um1") (pin "2") (pinfunction "PC13_2") (pintype "bidirectional"))
      (node (ref "header") (pin "16") (pinfunction "16_16") (pintype "passive"))
    )
    (net (code "29") (name "/NetLabel47") (class "Default")
      (node (ref "RJ3") (pin "2") (pinfunction "2_2") (pintype "passive"))
      (node (ref "Um1") (pin "3") (pinfunction "PC14-OSC32_IN_3") (pintype "bidirectional"))
    )
    (net (code "30") (name "/NetLabel48") (class "Default")
      (node (ref "RJ4") (pin "2") (pinfunction "2_2") (pintype "passive"))
      (node (ref "Um1") (pin "4") (pinfunction "PC15-OSC32_OUT_4") (pintype "bidirectional"))
    )
    (net (code "31") (name "/NetLabel60") (class "Default")
      (node (ref "Um1") (pin "1") (pinfunction "VBAT_1") (pintype "power_in"))
      (node (ref "header") (pin "24") (pinfunction "24_24") (pintype "passive"))
    )
    (net (code "32") (name "/NetLabel61") (class "Default")
      (node (ref "MCM UART") (pin "2") (pinfunction "2_2") (pintype "passive"))
      (node (ref "Um1") (pin "55") (pinfunction "PB3_55") (pintype "bidirectional"))
    )
    (net (code "33") (name "/NetLabel62") (class "Default")
      (node (ref "MCM UART") (pin "1") (pinfunction "1_1") (pintype "passive"))
      (node (ref "Um1") (pin "56") (pinfunction "PB4_56") (pintype "bidirectional"))
    )
    (net (code "34") (name "/NetLabel63") (class "Default")
      (node (ref "CMS UART") (pin "2") (pinfunction "2_2") (pintype "passive"))
      (node (ref "Um1") (pin "33") (pinfunction "PB12_33") (pintype "bidirectional"))
    )
    (net (code "35") (name "/NetLabel64") (class "Default")
      (node (ref "CMS UART") (pin "1") (pinfunction "1_1") (pintype "passive"))
      (node (ref "Um1") (pin "34") (pinfunction "PB13_34") (pintype "bidirectional"))
    )
    (net (code "36") (name "/NetLabel65") (class "Default")
      (node (ref "ECB UART") (pin "1") (pinfunction "1_1") (pintype "passive"))
      (node (ref "Um1") (pin "53") (pinfunction "PC12_53") (pintype "bidirectional"))
    )
    (net (code "37") (name "/NetLabel66") (class "Default")
      (node (ref "ECB UART") (pin "2") (pinfunction "2_2") (pintype "passive"))
      (node (ref "Um1") (pin "54") (pinfunction "PD2_54") (pintype "bidirectional"))
    )
    (net (code "38") (name "/NetLabel72") (class "Default")
      (node (ref "Um1") (pin "44") (pinfunction "PA11_44") (pintype "bidirectional"))
      (node (ref "header") (pin "4") (pinfunction "4_4") (pintype "passive"))
    )
    (net (code "39") (name "/NetLabel73") (class "Default")
      (node (ref "Um1") (pin "45") (pinfunction "PA12_45") (pintype "bidirectional"))
      (node (ref "header") (pin "5") (pinfunction "5_5") (pintype "passive"))
    )
    (net (code "40") (name "/NetLabel74") (class "Default")
      (node (ref "Um1") (pin "50") (pinfunction "PA15_50") (pintype "bidirectional"))
      (node (ref "header") (pin "19") (pinfunction "19_19") (pintype "passive"))
    )
    (net (code "41") (name "/PH0") (class "Default")
      (node (ref "RJ5") (pin "2") (pinfunction "2_2") (pintype "passive"))
      (node (ref "Um1") (pin "5") (pinfunction "PH0-OSC_IN_5") (pintype "bidirectional"))
    )
    (net (code "42") (name "/PH1") (class "Default")
      (node (ref "C33") (pin "2") (pinfunction "2_2") (pintype "passive"))
      (node (ref "Um1") (pin "6") (pinfunction "PH1_6") (pintype "bidirectional"))
      (node (ref "Y1") (pin "1") (pinfunction "1_1") (pintype "passive"))
    )
    (net (code "43") (name "/RIGHT") (class "Default")
      (node (ref "KEYPAD") (pin "4") (pinfunction "4_4") (pintype "passive"))
      (node (ref "Um1") (pin "21") (pinfunction "PA5_21") (pintype "bidirectional"))
    )
    (net (code "44") (name "/RST") (class "Default")
      (node (ref "C50") (pin "2") (pinfunction "2_2") (pintype "passive"))
      (node (ref "Micro_H") (pin "5") (pinfunction "5_5") (pintype "passive"))
      (node (ref "SW3") (pin "3") (pinfunction "3_3") (pintype "passive"))
      (node (ref "SW3") (pin "4") (pinfunction "4_4") (pintype "passive"))
      (node (ref "Um1") (pin "7") (pinfunction "NRST_7") (pintype "bidirectional"))
      (node (ref "Usup") (pin "2") (pinfunction "RESET_2") (pintype "passive"))
    )
    (net (code "45") (name "/SWCLK") (class "Default")
      (node (ref "Micro_H") (pin "2") (pinfunction "2_2") (pintype "passive"))
      (node (ref "Um1") (pin "49") (pinfunction "PA14_49") (pintype "bidirectional"))
    )
    (net (code "46") (name "/SWDIO") (class "Default")
      (node (ref "Micro_H") (pin "4") (pinfunction "4_4") (pintype "passive"))
      (node (ref "Um1") (pin "46") (pinfunction "PA13_46") (pintype "bidirectional"))
    )
    (net (code "47") (name "/Servo_Fuse") (class "Default")
      (node (ref "R30") (pin "1") (pinfunction "1_1") (pintype "passive"))
      (node (ref "Um1") (pin "8") (pinfunction "PC0_8") (pintype "input"))
    )
    (net (code "48") (name "/UP") (class "Default")
      (node (ref "KEYPAD") (pin "1") (pinfunction "1_1") (pintype "passive"))
      (node (ref "Um1") (pin "16") (pinfunction "PA2_16") (pintype "bidirectional"))
    )
    (net (code "49") (name "/con1_voltage") (class "Default")
      (node (ref "U9") (pin "5") (pinfunction "F_5") (pintype "output"))
    )
    (net (code "50") (name "/con_voltage") (class "Default")
      (node (ref "U9") (pin "4") (pinfunction "E_4") (pintype "output"))
    )
    (net (code "51") (name "/micro_relay") (class "Default")
      (node (ref "U9") (pin "6") (pinfunction "B_6") (pintype "input"))
      (node (ref "U9") (pin "7") (pinfunction "ENABLEB_7") (pintype "input"))
      (node (ref "Um1") (pin "26") (pinfunction "PB0_26") (pintype "bidirectional"))
    )
    (net (code "52") (name "3.3+") (class "Default")
      (node (ref "C1") (pin "2") (pinfunction "2_2") (pintype "passive"))
      (node (ref "C13") (pin "1") (pinfunction "1_1") (pintype "passive"))
      (node (ref "C2") (pin "2") (pinfunction "2_2") (pintype "passive"))
      (node (ref "C29") (pin "1") (pinfunction "1_1") (pintype "passive"))
      (node (ref "C3") (pin "2") (pinfunction "2_2") (pintype "passive"))
      (node (ref "C4") (pin "2") (pinfunction "2_2") (pintype "passive"))
      (node (ref "C51") (pin "2") (pinfunction "2_2") (pintype "passive"))
      (node (ref "C52") (pin "1") (pinfunction "1_1") (pintype "passive"))
      (node (ref "Co_6") (pin "1") (pinfunction "1_1") (pintype "passive"))
      (node (ref "L6") (pin "2") (pinfunction "2_2") (pintype "passive"))
      (node (ref "Micro_H") (pin "1") (pinfunction "1_1") (pintype "passive"))
      (node (ref "RJ2") (pin "1") (pinfunction "1_1") (pintype "passive"))
      (node (ref "Rf") (pin "2") (pinfunction "2_2") (pintype "passive"))
      (node (ref "SW2") (pin "3") (pinfunction "3_3") (pintype "passive"))
      (node (ref "U6") (pin "10") (pinfunction "VOUT_10") (pintype "input"))
      (node (ref "U9") (pin "1") (pinfunction "VCC_1") (pintype "power_in"))
      (node (ref "Um1") (pin "13") (pinfunction "VDDA/VREF+_13") (pintype "power_in"))
      (node (ref "Um1") (pin "19") (pinfunction "VDD_19") (pintype "power_in"))
      (node (ref "Um1") (pin "32") (pinfunction "VDD_32") (pintype "power_in"))
      (node (ref "Um1") (pin "48") (pinfunction "VDD_48") (pintype "power_in"))
      (node (ref "Um1") (pin "64") (pinfunction "VDD_64") (pintype "power_in"))
      (node (ref "Usup") (pin "3") (pinfunction "VDD_3") (pintype "power_in"))
    )
    (net (code "53") (name "12V_SUPPLY") (class "Default")
      (node (ref "Ct7") (pin "1") (pinfunction "C_1") (pintype "passive"))
      (node (ref "L1_7") (pin "1") (pinfunction "1_1") (pintype "passive"))
      (node (ref "Rf7") (pin "1") (pinfunction "1_1") (pintype "passive"))
      (node (ref "U7") (pin "10") (pinfunction "VOUT_10") (pintype "input"))
      (node (ref "U9") (pin "16") (pinfunction "VDD_16") (pintype "power_in"))
    )
    (net (code "54") (name "DGND") (class "Default")
      (node (ref "C1") (pin "1") (pinfunction "1_1") (pintype "passive"))
      (node (ref "C13") (pin "2") (pinfunction "2_2") (pintype "passive"))
      (node (ref "C2") (pin "1") (pinfunction "1_1") (pintype "passive"))
      (node (ref "C29") (pin "2") (pinfunction "2_2") (pintype "passive"))
      (node (ref "C3") (pin "1") (pinfunction "1_1") (pintype "passive"))
      (node (ref "C32") (pin "1") (pinfunction "1_1") (pintype "passive"))
      (node (ref "C33") (pin "1") (pinfunction "1_1") (pintype "passive"))
      (node (ref "C34") (pin "1") (pinfunction "1_1") (pintype "passive"))
      (node (ref "C35") (pin "1") (pinfunction "1_1") (pintype "passive"))
      (node (ref "C4") (pin "1") (pinfunction "1_1") (pintype "passive"))
      (node (ref "C50") (pin "1") (pinfunction "1_1") (pintype "passive"))
      (node (ref "C51") (pin "1") (pinfunction "1_1") (pintype "passive"))
      (node (ref "C52") (pin "2") (pinfunction "2_2") (pintype "passive"))
      (node (ref "C53") (pin "2") (pinfunction "2_2") (pintype "passive"))
      (node (ref "CMS UART") (pin "3") (pinfunction "3_3") (pintype "passive"))
      (node (ref "D11") (pin "1") (pinfunction "K_1") (pintype "passive"))
      (node (ref "ECB UART") (pin "3") (pinfunction "3_3") (pintype "passive"))
      (node (ref "KEYPAD") (pin "MP1") (pinfunction "MP1_MP1") (pintype "passive"))
      (node (ref "KEYPAD") (pin "MP2") (pinfunction "MP2_MP2") (pintype "passive"))
      (node (ref "LCD DISPLAY I2C") (pin "2") (pinfunction "2_2") (pintype "passive"))
      (node (ref "MCM UART") (pin "3") (pinfunction "3_3") (pintype "passive"))
      (node (ref "Micro_H") (pin "3") (pinfunction "3_3") (pintype "passive"))
      (node (ref "Micro_H") (pin "6") (pinfunction "6_6") (pintype "passive"))
      (node (ref "NT1") (pin "1") (pinfunction "1_1") (pintype "passive"))
      (node (ref "R30") (pin "2") (pinfunction "2_2") (pintype "passive"))
      (node (ref "R31") (pin "2") (pinfunction "2_2") (pintype "passive"))
      (node (ref "R32") (pin "2") (pinfunction "2_2") (pintype "passive"))
      (node (ref "R33") (pin "2") (pinfunction "2_2") (pintype "passive"))
      (node (ref "R34") (pin "2") (pinfunction "2_2") (pintype "passive"))
      (node (ref "R35") (pin "2") (pinfunction "2_2") (pintype "passive"))
      (node (ref "R36") (pin "2") (pinfunction "2_2") (pintype "passive"))
      (node (ref "R37") (pin "2") (pinfunction "2_2") (pintype "passive"))
      (node (ref "R38") (pin "2") (pinfunction "2_2") (pintype "passive"))
      (node (ref "R50") (pin "2") (pinfunction "2_2") (pintype "passive"))
      (node (ref "RJ1") (pin "1") (pinfunction "1_1") (pintype "passive"))
      (node (ref "SW3") (pin "1") (pinfunction "1_1") (pintype "passive"))
      (node (ref "SW3") (pin "2") (pinfunction "2_2") (pintype "passive"))
      (node (ref "U9") (pin "8") (pinfunction "VSS_8") (pintype "power_in"))
      (node (ref "Um1") (pin "12") (pinfunction "VSSA/VREF-_12") (pintype "power_in"))
      (node (ref "Um1") (pin "18") (pinfunction "VSS_18") (pintype "power_in"))
      (node (ref "Um1") (pin "31") (pinfunction "VSS_31") (pintype "power_in"))
      (node (ref "Um1") (pin "47") (pinfunction "VSS_47") (pintype "power_in"))
      (node (ref "Um1") (pin "63") (pinfunction "VSS_63") (pintype "power_in"))
      (node (ref "Usup") (pin "1") (pinfunction "GND_1") (pintype "power_in"))
      (node (ref "header") (pin "20") (pinfunction "20_20") (pintype "passive"))
      (node (ref "header") (pin "6") (pinfunction "6_6") (pintype "passive"))
    )
    (net (code "55") (name "GND") (class "Default")
      (node (ref "Ci6") (pin "2") (pinfunction "2_2") (pintype "passive"))
      (node (ref "Ci7") (pin "2") (pinfunction "2_2") (pintype "passive"))
      (node (ref "Co_6") (pin "2") (pinfunction "2_2") (pintype "passive"))
      (node (ref "Cr") (pin "2") (pinfunction "2_2") (pintype "passive"))
      (node (ref "Cr7") (pin "2") (pinfunction "2_2") (pintype "passive"))
      (node (ref "Cs") (pin "1") (pinfunction "1_1") (pintype "passive"))
      (node (ref "Cs7") (pin "1") (pinfunction "1_1") (pintype "passive"))
      (node (ref "Ct7") (pin "2") (pinfunction "A_2") (pintype "passive"))
      (node (ref "Cv") (pin "1") (pinfunction "1_1") (pintype "passive"))
      (node (ref "Cv7") (pin "1") (pinfunction "1_1") (pintype "passive"))
      (node (ref "Cx6") (pin "2") (pinfunction "2_2") (pintype "passive"))
      (node (ref "Cx7") (pin "2") (pinfunction "2_2") (pintype "passive"))
      (node (ref "NT1") (pin "2") (pinfunction "2_2") (pintype "passive"))
      (node (ref "RU2") (pin "1") (pinfunction "1_1") (pintype "passive"))
      (node (ref "R_SW") (pin "1") (pinfunction "1_1") (pintype "passive"))
      (node (ref "Rb7") (pin "1") (pinfunction "1_1") (pintype "passive"))
      (node (ref "Rfb") (pin "1") (pinfunction "1_1") (pintype "passive"))
      (node (ref "Rs") (pin "1") (pinfunction "1_1") (pintype "passive"))
      (node (ref "Rs7") (pin "2") (pinfunction "2_2") (pintype "passive"))
      (node (ref "Rt") (pin "2") (pinfunction "2_2") (pintype "passive"))
      (node (ref "Rt7") (pin "2") (pinfunction "2_2") (pintype "passive"))
      (node (ref "Ruv7") (pin "1") (pinfunction "1_1") (pintype "passive"))
      (node (ref "U6") (pin "11") (pinfunction "DEMB_11") (pintype "passive"))
      (node (ref "U6") (pin "13") (pinfunction "CSG_13") (pintype "passive"))
      (node (ref "U6") (pin "14") (pinfunction "PGND_14") (pintype "power_in"))
      (node (ref "U6") (pin "17") (pinfunction "VCCX_17") (pintype "power_in"))
      (node (ref "U6") (pin "21") (pinfunction "EP_21") (pintype "power_in"))
      (node (ref "U6") (pin "6") (pinfunction "AGND_6") (pintype "power_in"))
      (node (ref "U7") (pin "11") (pinfunction "DEMB_11") (pintype "passive"))
      (node (ref "U7") (pin "13") (pinfunction "CSG_13") (pintype "passive"))
      (node (ref "U7") (pin "14") (pinfunction "PGND_14") (pintype "power_in"))
      (node (ref "U7") (pin "17") (pinfunction "VCCX_17") (pintype "power_in"))
      (node (ref "U7") (pin "21") (pinfunction "EP_21") (pintype "power_in"))
      (node (ref "U7") (pin "6") (pinfunction "AGND_6") (pintype "power_in"))
    )
    (net (code "56") (name "Net-(C32-Pad2)") (class "Default")
      (node (ref "C32") (pin "2") (pinfunction "2_2") (pintype "passive"))
      (node (ref "RJ5") (pin "1") (pinfunction "1_1") (pintype "passive"))
      (node (ref "Y1") (pin "2") (pinfunction "2_2") (pintype "passive"))
    )
    (net (code "57") (name "Net-(C34-Pad2)") (class "Default")
      (node (ref "C34") (pin "2") (pinfunction "2_2") (pintype "passive"))
      (node (ref "RJ4") (pin "1") (pinfunction "1_1") (pintype "passive"))
      (node (ref "Y2") (pin "1") (pinfunction "1_1") (pintype "passive"))
    )
    (net (code "58") (name "Net-(C35-Pad2)") (class "Default")
      (node (ref "C35") (pin "2") (pinfunction "2_2") (pintype "passive"))
      (node (ref "RJ3") (pin "1") (pinfunction "1_1") (pintype "passive"))
      (node (ref "Y2") (pin "2") (pinfunction "2_2") (pintype "passive"))
    )
    (net (code "59") (name "Net-(Cc72-Pad1)") (class "Default")
      (node (ref "Cc72") (pin "1") (pinfunction "1_1") (pintype "passive"))
      (node (ref "Rc7") (pin "2") (pinfunction "2_2") (pintype "passive"))
    )
    (net (code "60") (name "Net-(Cc_6-Pad1)") (class "Default")
      (node (ref "Cc_6") (pin "1") (pinfunction "1_1") (pintype "passive"))
      (node (ref "Rc") (pin "2") (pinfunction "2_2") (pintype "passive"))
    )
    (net (code "61") (name "Net-(D11-A)") (class "Default")
      (node (ref "D11") (pin "2") (pinfunction "A_2") (pintype "passive"))
      (node (ref "R10") (pin "2") (pinfunction "2_2") (pintype "passive"))
    )
    (net (code "62") (name "Net-(M1_7-D)") (class "Default")
      (node (ref "Ci6") (pin "1") (pinfunction "1_1") (pintype "passive"))
      (node (ref "Ci7") (pin "1") (pinfunction "1_1") (pintype "passive"))
      (node (ref "Cx6") (pin "1") (pinfunction "1_1") (pintype "passive"))
      (node (ref "Cx7") (pin "1") (pinfunction "1_1") (pintype "passive"))
      (node (ref "M1_7") (pin "5-6-7-8") (pinfunction "D_5-6-7-8") (pintype "passive"))
      (node (ref "ON/OFF SW") (pin "1") (pinfunction "1_1") (pintype "passive"))
      (node (ref "Q6_1") (pin "5-6-7-8") (pinfunction "D_5-6-7-8") (pintype "passive"))
      (node (ref "RU1") (pin "1") (pinfunction "1_1") (pintype "passive"))
      (node (ref "R_SW") (pin "2") (pinfunction "2_2") (pintype "passive"))
      (node (ref "Re7") (pin "1") (pinfunction "1_1") (pintype "passive"))
      (node (ref "Ren") (pin "1") (pinfunction "1_1") (pintype "passive"))
      (node (ref "Ru7") (pin "1") (pinfunction "1_1") (pintype "passive"))
      (node (ref "U6") (pin "1") (pinfunction "VIN_1") (pintype "power_in"))
      (node (ref "U7") (pin "1") (pinfunction "VIN_1") (pintype "power_in"))
    )
    (net (code "63") (name "Net-(M1_7-G)") (class "Default")
      (node (ref "M1_7") (pin "4") (pinfunction "G_4") (pintype "passive"))
      (node (ref "U7") (pin "19") (pinfunction "HO_19") (pintype "output"))
    )
    (net (code "64") (name "Net-(M2_7-D)") (class "Default")
      (node (ref "Cb71") (pin "1") (pinfunction "1_1") (pintype "passive"))
      (node (ref "L1_7") (pin "2") (pinfunction "2_2") (pintype "passive"))
      (node (ref "M1_7") (pin "1") (pinfunction "S_1") (pintype "passive"))
      (node (ref "M1_7") (pin "2") (pinfunction "S_2") (pintype "passive"))
      (node (ref "M1_7") (pin "3") (pinfunction "S_3") (pintype "passive"))
      (node (ref "M2_7") (pin "5-6-7-8") (pinfunction "D_5-6-7-8") (pintype "passive"))
      (node (ref "U7") (pin "20") (pinfunction "SW_20") (pintype "power_in"))
    )
    (net (code "65") (name "Net-(M2_7-G)") (class "Default")
      (node (ref "M2_7") (pin "4") (pinfunction "G_4") (pintype "passive"))
      (node (ref "U7") (pin "15") (pinfunction "LO_15") (pintype "output"))
    )
    (net (code "66") (name "Net-(ON/OFF SW-Pad3)") (class "Default")
      (node (ref "ON/OFF SW") (pin "3") (pinfunction "3_3") (pintype "passive"))
      (node (ref "RL") (pin "2") (pinfunction "2_2") (pintype "passive"))
    )
    (net (code "67") (name "Net-(Q6_1-G)") (class "Default")
      (node (ref "Q6_1") (pin "4") (pinfunction "G_4") (pintype "passive"))
      (node (ref "U6") (pin "19") (pinfunction "HO_19") (pintype "output"))
    )
    (net (code "68") (name "Net-(Q6_2-D)") (class "Default")
      (node (ref "Cb") (pin "1") (pinfunction "1_1") (pintype "passive"))
      (node (ref "L6") (pin "1") (pinfunction "1_1") (pintype "passive"))
      (node (ref "Q6_1") (pin "1") (pinfunction "S_1") (pintype "passive"))
      (node (ref "Q6_1") (pin "2") (pinfunction "S_2") (pintype "passive"))
      (node (ref "Q6_1") (pin "3") (pinfunction "S_3") (pintype "passive"))
      (node (ref "Q6_2") (pin "5-6-7-8") (pinfunction "D_5-6-7-8") (pintype "passive"))
      (node (ref "U6") (pin "20") (pinfunction "SW_20") (pintype "power_in"))
    )
    (net (code "69") (name "Net-(Q6_2-G)") (class "Default")
      (node (ref "Q6_2") (pin "4") (pinfunction "G_4") (pintype "passive"))
      (node (ref "U6") (pin "15") (pinfunction "LO_15") (pintype "output"))
    )
    (net (code "70") (name "Net-(R50-Pad1)") (class "Default")
      (node (ref "R50") (pin "1") (pinfunction "1_1") (pintype "passive"))
      (node (ref "SW2") (pin "1") (pinfunction "1_1") (pintype "passive"))
    )
    (net (code "71") (name "Net-(SW2-C)") (class "Default")
      (node (ref "SW2") (pin "2") (pinfunction "C_2") (pintype "passive"))
      (node (ref "Um1") (pin "60") (pinfunction "BOOT0_60") (pintype "input"))
    )
    (net (code "72") (name "Net-(U6-COMP)") (class "Default")
      (node (ref "Cc6") (pin "2") (pinfunction "2_2") (pintype "passive"))
      (node (ref "Cc_6") (pin "2") (pinfunction "2_2") (pintype "passive"))
      (node (ref "U6") (pin "9") (pinfunction "COMP_9") (pintype "output"))
    )
    (net (code "73") (name "Net-(U6-CS)") (class "Default")
      (node (ref "Q6_2") (pin "1") (pinfunction "S_1") (pintype "passive"))
      (node (ref "Q6_2") (pin "2") (pinfunction "S_2") (pintype "passive"))
      (node (ref "Q6_2") (pin "3") (pinfunction "S_3") (pintype "passive"))
      (node (ref "Rs") (pin "2") (pinfunction "2_2") (pintype "passive"))
      (node (ref "U6") (pin "12") (pinfunction "CS_12") (pintype "input"))
    )
    (net (code "74") (name "Net-(U6-EN)") (class "Default")
      (node (ref "Ren") (pin "2") (pinfunction "2_2") (pintype "passive"))
      (node (ref "U6") (pin "4") (pinfunction "EN_4") (pintype "input"))
    )
    (net (code "75") (name "Net-(U6-FB)") (class "Default")
      (node (ref "Cc6") (pin "1") (pinfunction "1_1") (pintype "passive"))
      (node (ref "Rc") (pin "1") (pinfunction "1_1") (pintype "passive"))
      (node (ref "Rf") (pin "1") (pinfunction "1_1") (pintype "passive"))
      (node (ref "Rfb") (pin "2") (pinfunction "2_2") (pintype "passive"))
      (node (ref "U6") (pin "8") (pinfunction "FB_8") (pintype "input"))
    )
    (net (code "76") (name "Net-(U6-HB)") (class "Default")
      (node (ref "Cb") (pin "2") (pinfunction "2_2") (pintype "passive"))
      (node (ref "D6") (pin "1") (pinfunction "1_1") (pintype "passive"))
      (node (ref "U6") (pin "18") (pinfunction "HB_18") (pintype "passive"))
    )
    (net (code "77") (name "Net-(U6-RAMP)") (class "Default")
      (node (ref "Cr") (pin "1") (pinfunction "1_1") (pintype "passive"))
      (node (ref "U6") (pin "5") (pinfunction "RAMP_5") (pintype "input"))
    )
    (net (code "78") (name "Net-(U6-RT{slash}SYNC)") (class "Default")
      (node (ref "Rt") (pin "1") (pinfunction "1_1") (pintype "passive"))
      (node (ref "U6") (pin "3") (pinfunction "RT/SYNC_3") (pintype "input"))
    )
    (net (code "79") (name "Net-(U6-SS)") (class "Default")
      (node (ref "Cs") (pin "2") (pinfunction "2_2") (pintype "passive"))
      (node (ref "U6") (pin "7") (pinfunction "SS_7") (pintype "input"))
    )
    (net (code "80") (name "Net-(U6-ULVO)") (class "Default")
      (node (ref "RU1") (pin "2") (pinfunction "2_2") (pintype "passive"))
      (node (ref "RU2") (pin "2") (pinfunction "2_2") (pintype "passive"))
      (node (ref "U6") (pin "2") (pinfunction "ULVO_2") (pintype "input"))
    )
    (net (code "81") (name "Net-(U6-VCC)") (class "Default")
      (node (ref "Cv") (pin "2") (pinfunction "2_2") (pintype "passive"))
      (node (ref "D6") (pin "2") (pinfunction "2_2") (pintype "passive"))
      (node (ref "U6") (pin "16") (pinfunction "VCC_16") (pintype "power_in"))
    )
    (net (code "82") (name "Net-(U7-COMP)") (class "Default")
      (node (ref "Cc7") (pin "1") (pinfunction "1_1") (pintype "passive"))
      (node (ref "Cc72") (pin "2") (pinfunction "2_2") (pintype "passive"))
      (node (ref "U7") (pin "9") (pinfunction "COMP_9") (pintype "output"))
    )
    (net (code "83") (name "Net-(U7-CS)") (class "Default")
      (node (ref "M2_7") (pin "1") (pinfunction "S_1") (pintype "passive"))
      (node (ref "M2_7") (pin "2") (pinfunction "S_2") (pintype "passive"))
      (node (ref "M2_7") (pin "3") (pinfunction "S_3") (pintype "passive"))
      (node (ref "Rs7") (pin "1") (pinfunction "1_1") (pintype "passive"))
      (node (ref "U7") (pin "12") (pinfunction "CS_12") (pintype "input"))
    )
    (net (code "84") (name "Net-(U7-EN)") (class "Default")
      (node (ref "Re7") (pin "2") (pinfunction "2_2") (pintype "passive"))
      (node (ref "U7") (pin "4") (pinfunction "EN_4") (pintype "input"))
    )
    (net (code "85") (name "Net-(U7-FB)") (class "Default")
      (node (ref "Cc7") (pin "2") (pinfunction "2_2") (pintype "passive"))
      (node (ref "Rb7") (pin "2") (pinfunction "2_2") (pintype "passive"))
      (node (ref "Rc7") (pin "1") (pinfunction "1_1") (pintype "passive"))
      (node (ref "Rf7") (pin "2") (pinfunction "2_2") (pintype "passive"))
      (node (ref "U7") (pin "8") (pinfunction "FB_8") (pintype "input"))
    )
    (net (code "86") (name "Net-(U7-HB)") (class "Default")
      (node (ref "Cb71") (pin "2") (pinfunction "2_2") (pintype "passive"))
      (node (ref "D7") (pin "1") (pinfunction "1_1") (pintype "passive"))
      (node (ref "U7") (pin "18") (pinfunction "HB_18") (pintype "passive"))
    )
    (net (code "87") (name "Net-(U7-RAMP)") (class "Default")
      (node (ref "Cr7") (pin "1") (pinfunction "1_1") (pintype "passive"))
      (node (ref "U7") (pin "5") (pinfunction "RAMP_5") (pintype "input"))
    )
    (net (code "88") (name "Net-(U7-RT{slash}SYNC)") (class "Default")
      (node (ref "Rt7") (pin "1") (pinfunction "1_1") (pintype "passive"))
      (node (ref "U7") (pin "3") (pinfunction "RT/SYNC_3") (pintype "input"))
    )
    (net (code "89") (name "Net-(U7-SS)") (class "Default")
      (node (ref "Cs7") (pin "2") (pinfunction "2_2") (pintype "passive"))
      (node (ref "U7") (pin "7") (pinfunction "SS_7") (pintype "input"))
    )
    (net (code "90") (name "Net-(U7-ULVO)") (class "Default")
      (node (ref "Ru7") (pin "2") (pinfunction "2_2") (pintype "passive"))
      (node (ref "Ruv7") (pin "2") (pinfunction "2_2") (pintype "passive"))
      (node (ref "U7") (pin "2") (pinfunction "ULVO_2") (pintype "input"))
    )
    (net (code "91") (name "Net-(U7-VCC)") (class "Default")
      (node (ref "Cv7") (pin "2") (pinfunction "2_2") (pintype "passive"))
      (node (ref "D7") (pin "2") (pinfunction "2_2") (pintype "passive"))
      (node (ref "U7") (pin "16") (pinfunction "VCC_16") (pintype "power_in"))
    )
    (net (code "92") (name "Net-(Um1A-PB14)") (class "Default")
      (node (ref "LCD DISPLAY I2C") (pin "3") (pinfunction "3_3") (pintype "passive"))
      (node (ref "Um1") (pin "35") (pinfunction "PB14_35") (pintype "bidirectional"))
    )
    (net (code "93") (name "Net-(Um1A-PB15)") (class "Default")
      (node (ref "LCD DISPLAY I2C") (pin "4") (pinfunction "4_4") (pintype "passive"))
      (node (ref "Um1") (pin "36") (pinfunction "PB15_36") (pintype "bidirectional"))
    )
    (net (code "94") (name "Net-(Um1B-VCAP_1)") (class "Default")
      (node (ref "C53") (pin "1") (pinfunction "1_1") (pintype "passive"))
      (node (ref "Um1") (pin "30") (pinfunction "VCAP_1_30") (pintype "power_in"))
    )
    (net (code "95") (name "System+") (class "Default")
      (node (ref "RL") (pin "1") (pinfunction "1_1") (pintype "passive"))
    )
    (net (code "96") (name "unconnected-(ON/OFF SW-Pad2)") (class "Default")
      (node (ref "ON/OFF SW") (pin "2") (pinfunction "2_2") (pintype "passive"))
    )
    (net (code "97") (name "unconnected-(U9-C-Pad10)") (class "Default")
      (node (ref "U9") (pin "10") (pinfunction "C_10") (pintype "input+no_connect"))
    )
    (net (code "98") (name "unconnected-(U9-D-Pad14)") (class "Default")
      (node (ref "U9") (pin "14") (pinfunction "D_14") (pintype "input+no_connect"))
    )
    (net (code "99") (name "unconnected-(U9-ENABLEC-Pad9)") (class "Default")
      (node (ref "U9") (pin "9") (pinfunction "ENABLEC_9") (pintype "input+no_connect"))
    )
    (net (code "100") (name "unconnected-(U9-ENABLED-Pad15)") (class "Default")
      (node (ref "U9") (pin "15") (pinfunction "ENABLED_15") (pintype "input+no_connect"))
    )
    (net (code "101") (name "unconnected-(U9-G-Pad11)") (class "Default")
      (node (ref "U9") (pin "11") (pinfunction "G_11") (pintype "output"))
    )
    (net (code "102") (name "unconnected-(U9-H-Pad13)") (class "Default")
      (node (ref "U9") (pin "13") (pinfunction "H_13") (pintype "output"))
    )
    (net (code "103") (name "unconnected-(U9-NC-Pad12)") (class "Default")
      (node (ref "U9") (pin "12") (pinfunction "NC_12") (pintype "passive"))
    )
    (net (code "104") (name "unconnected-(Um1A-PA0-Pad14)") (class "Default")
      (node (ref "Um1") (pin "14") (pinfunction "PA0_14") (pintype "bidirectional"))
    )
    (net (code "105") (name "unconnected-(Um1A-PA1-Pad15)") (class "Default")
      (node (ref "Um1") (pin "15") (pinfunction "PA1_15") (pintype "bidirectional"))
    )
    (net (code "106") (name "unconnected-(header-Pad13)") (class "Default")
      (node (ref "header") (pin "13") (pinfunction "13_13") (pintype "passive"))
    )
    (net (code "107") (name "unconnected-(header-Pad17)") (class "Default")
      (node (ref "header") (pin "17") (pinfunction "17_17") (pintype "passive"))
    )
    (net (code "108") (name "unconnected-(header-Pad18)") (class "Default")
      (node (ref "header") (pin "18") (pinfunction "18_18") (pintype "passive"))
    )
    (net (code "109") (name "unconnected-(header-Pad23)") (class "Default")
      (node (ref "header") (pin "23") (pinfunction "23_23") (pintype "passive"))
    )
  )
)
